# DSO_Counters.net
KiCad netlist of a schematic drawn in Altium Designer
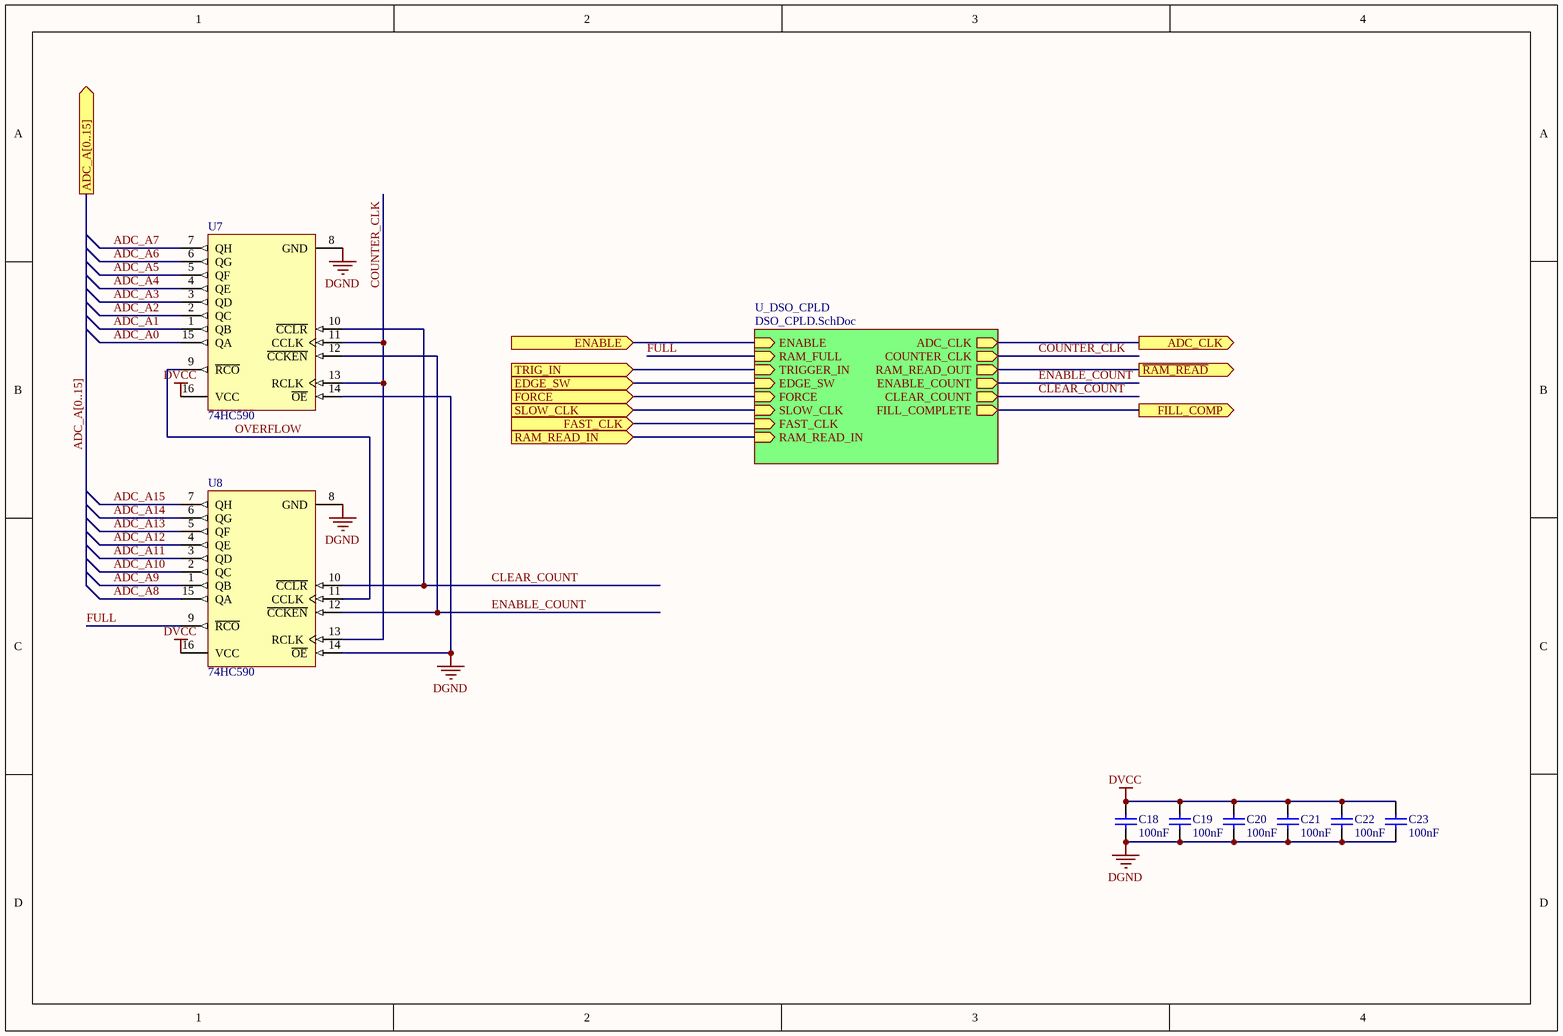
[diagram p0: DSO_Counters.SchDoc]

(export (version "E")
  (design (tool "Eeschema 10.0.6"))
  (components
    (comp (ref "C18")
      (value "100nF")
      (footprint "0805C")
      (description "Capacitor")
      (fields (field (name "REVIEWED BY") "RM - 2018/08/05"))
      (libsource (lib "DSO") (part "C"))
    )
    (comp (ref "C19")
      (value "100nF")
      (footprint "0805C")
      (description "Capacitor")
      (fields (field (name "REVIEWED BY") "RM - 2018/08/05"))
      (libsource (lib "DSO") (part "C"))
    )
    (comp (ref "C20")
      (value "100nF")
      (footprint "0805C")
      (description "Capacitor")
      (fields (field (name "REVIEWED BY") "RM - 2018/08/05"))
      (libsource (lib "DSO") (part "C"))
    )
    (comp (ref "C21")
      (value "100nF")
      (footprint "0805C")
      (description "Capacitor")
      (fields (field (name "REVIEWED BY") "RM - 2018/08/05"))
      (libsource (lib "DSO") (part "C"))
    )
    (comp (ref "C22")
      (value "100nF")
      (footprint "0805C")
      (description "Capacitor")
      (fields (field (name "REVIEWED BY") "RM - 2018/08/05"))
      (libsource (lib "DSO") (part "C"))
    )
    (comp (ref "C23")
      (value "100nF")
      (footprint "0805C")
      (description "Capacitor")
      (fields (field (name "REVIEWED BY") "RM - 2018/08/05"))
      (libsource (lib "DSO") (part "C"))
    )
    (comp (ref "U7")
      (value "74HC590")
      (footprint "SOIC-16")
      (description "8-Bit Binary Counter Register")
      (fields (field (name "REVIEWED BY") "RM - 2018/08/05"))
      (libsource (lib "DSO") (part "74HC590"))
    )
    (comp (ref "U8")
      (value "74HC590")
      (footprint "SOIC-16")
      (description "8-Bit Binary Counter Register")
      (fields (field (name "REVIEWED BY") "RM - 2018/08/05"))
      (libsource (lib "DSO") (part "74HC590"))
    )
  )
  (nets
    (net (code "1") (name "/ADC_A0") (class "Default")
      (node (ref "U7") (pin "15") (pinfunction "QA_15") (pintype "output"))
    )
    (net (code "2") (name "/ADC_A1") (class "Default")
      (node (ref "U7") (pin "1") (pinfunction "QB_1") (pintype "output"))
    )
    (net (code "3") (name "/ADC_A2") (class "Default")
      (node (ref "U7") (pin "2") (pinfunction "QC_2") (pintype "output"))
    )
    (net (code "4") (name "/ADC_A3") (class "Default")
      (node (ref "U7") (pin "3") (pinfunction "QD_3") (pintype "output"))
    )
    (net (code "5") (name "/ADC_A4") (class "Default")
      (node (ref "U7") (pin "4") (pinfunction "QE_4") (pintype "output"))
    )
    (net (code "6") (name "/ADC_A5") (class "Default")
      (node (ref "U7") (pin "5") (pinfunction "QF_5") (pintype "output"))
    )
    (net (code "7") (name "/ADC_A6") (class "Default")
      (node (ref "U7") (pin "6") (pinfunction "QG_6") (pintype "output"))
    )
    (net (code "8") (name "/ADC_A7") (class "Default")
      (node (ref "U7") (pin "7") (pinfunction "QH_7") (pintype "output"))
    )
    (net (code "9") (name "/ADC_A8") (class "Default")
      (node (ref "U8") (pin "15") (pinfunction "QA_15") (pintype "output"))
    )
    (net (code "10") (name "/ADC_A9") (class "Default")
      (node (ref "U8") (pin "1") (pinfunction "QB_1") (pintype "output"))
    )
    (net (code "11") (name "/ADC_A10") (class "Default")
      (node (ref "U8") (pin "2") (pinfunction "QC_2") (pintype "output"))
    )
    (net (code "12") (name "/ADC_A11") (class "Default")
      (node (ref "U8") (pin "3") (pinfunction "QD_3") (pintype "output"))
    )
    (net (code "13") (name "/ADC_A12") (class "Default")
      (node (ref "U8") (pin "4") (pinfunction "QE_4") (pintype "output"))
    )
    (net (code "14") (name "/ADC_A13") (class "Default")
      (node (ref "U8") (pin "5") (pinfunction "QF_5") (pintype "output"))
    )
    (net (code "15") (name "/ADC_A14") (class "Default")
      (node (ref "U8") (pin "6") (pinfunction "QG_6") (pintype "output"))
    )
    (net (code "16") (name "/ADC_A15") (class "Default")
      (node (ref "U8") (pin "7") (pinfunction "QH_7") (pintype "output"))
    )
    (net (code "19") (name "/CLEAR_COUNT") (class "Default")
      (node (ref "U7") (pin "10") (pinfunction "~{CCLR}_10") (pintype "input"))
      (node (ref "U8") (pin "10") (pinfunction "~{CCLR}_10") (pintype "input"))
    )
    (net (code "20") (name "/COUNTER_CLK") (class "Default")
      (node (ref "U7") (pin "11") (pinfunction "CCLK_11") (pintype "input"))
      (node (ref "U7") (pin "13") (pinfunction "RCLK_13") (pintype "input"))
      (node (ref "U8") (pin "13") (pinfunction "RCLK_13") (pintype "input"))
    )
    (net (code "23") (name "/ENABLE_COUNT") (class "Default")
      (node (ref "U7") (pin "12") (pinfunction "~{CCKEN}_12") (pintype "input"))
      (node (ref "U8") (pin "12") (pinfunction "~{CCKEN}_12") (pintype "input"))
    )
    (net (code "27") (name "/FULL") (class "Default")
      (node (ref "U8") (pin "9") (pinfunction "~{RCO}_9") (pintype "output"))
    )
    (net (code "28") (name "/OVERFLOW") (class "Default")
      (node (ref "U7") (pin "9") (pinfunction "~{RCO}_9") (pintype "output"))
      (node (ref "U8") (pin "11") (pinfunction "CCLK_11") (pintype "input"))
    )
    (net (code "33") (name "DGND") (class "Default")
      (node (ref "C18") (pin "2") (pinfunction "2_2") (pintype "passive"))
      (node (ref "C19") (pin "2") (pinfunction "2_2") (pintype "passive"))
      (node (ref "C20") (pin "2") (pinfunction "2_2") (pintype "passive"))
      (node (ref "C21") (pin "2") (pinfunction "2_2") (pintype "passive"))
      (node (ref "C22") (pin "2") (pinfunction "2_2") (pintype "passive"))
      (node (ref "C23") (pin "2") (pinfunction "2_2") (pintype "passive"))
      (node (ref "U7") (pin "14") (pinfunction "~{OE}_14") (pintype "input"))
      (node (ref "U7") (pin "8") (pinfunction "GND_8") (pintype "power_in"))
      (node (ref "U8") (pin "14") (pinfunction "~{OE}_14") (pintype "input"))
      (node (ref "U8") (pin "8") (pinfunction "GND_8") (pintype "power_in"))
    )
    (net (code "34") (name "DVCC") (class "Default")
      (node (ref "C18") (pin "1") (pinfunction "1_1") (pintype "passive"))
      (node (ref "C19") (pin "1") (pinfunction "1_1") (pintype "passive"))
      (node (ref "C20") (pin "1") (pinfunction "1_1") (pintype "passive"))
      (node (ref "C21") (pin "1") (pinfunction "1_1") (pintype "passive"))
      (node (ref "C22") (pin "1") (pinfunction "1_1") (pintype "passive"))
      (node (ref "C23") (pin "1") (pinfunction "1_1") (pintype "passive"))
      (node (ref "U7") (pin "16") (pinfunction "VCC_16") (pintype "power_in"))
      (node (ref "U8") (pin "16") (pinfunction "VCC_16") (pintype "power_in"))
    )
  )
)
